# ltc4063-test.net
KiCad netlist of a schematic drawn in EAGLE
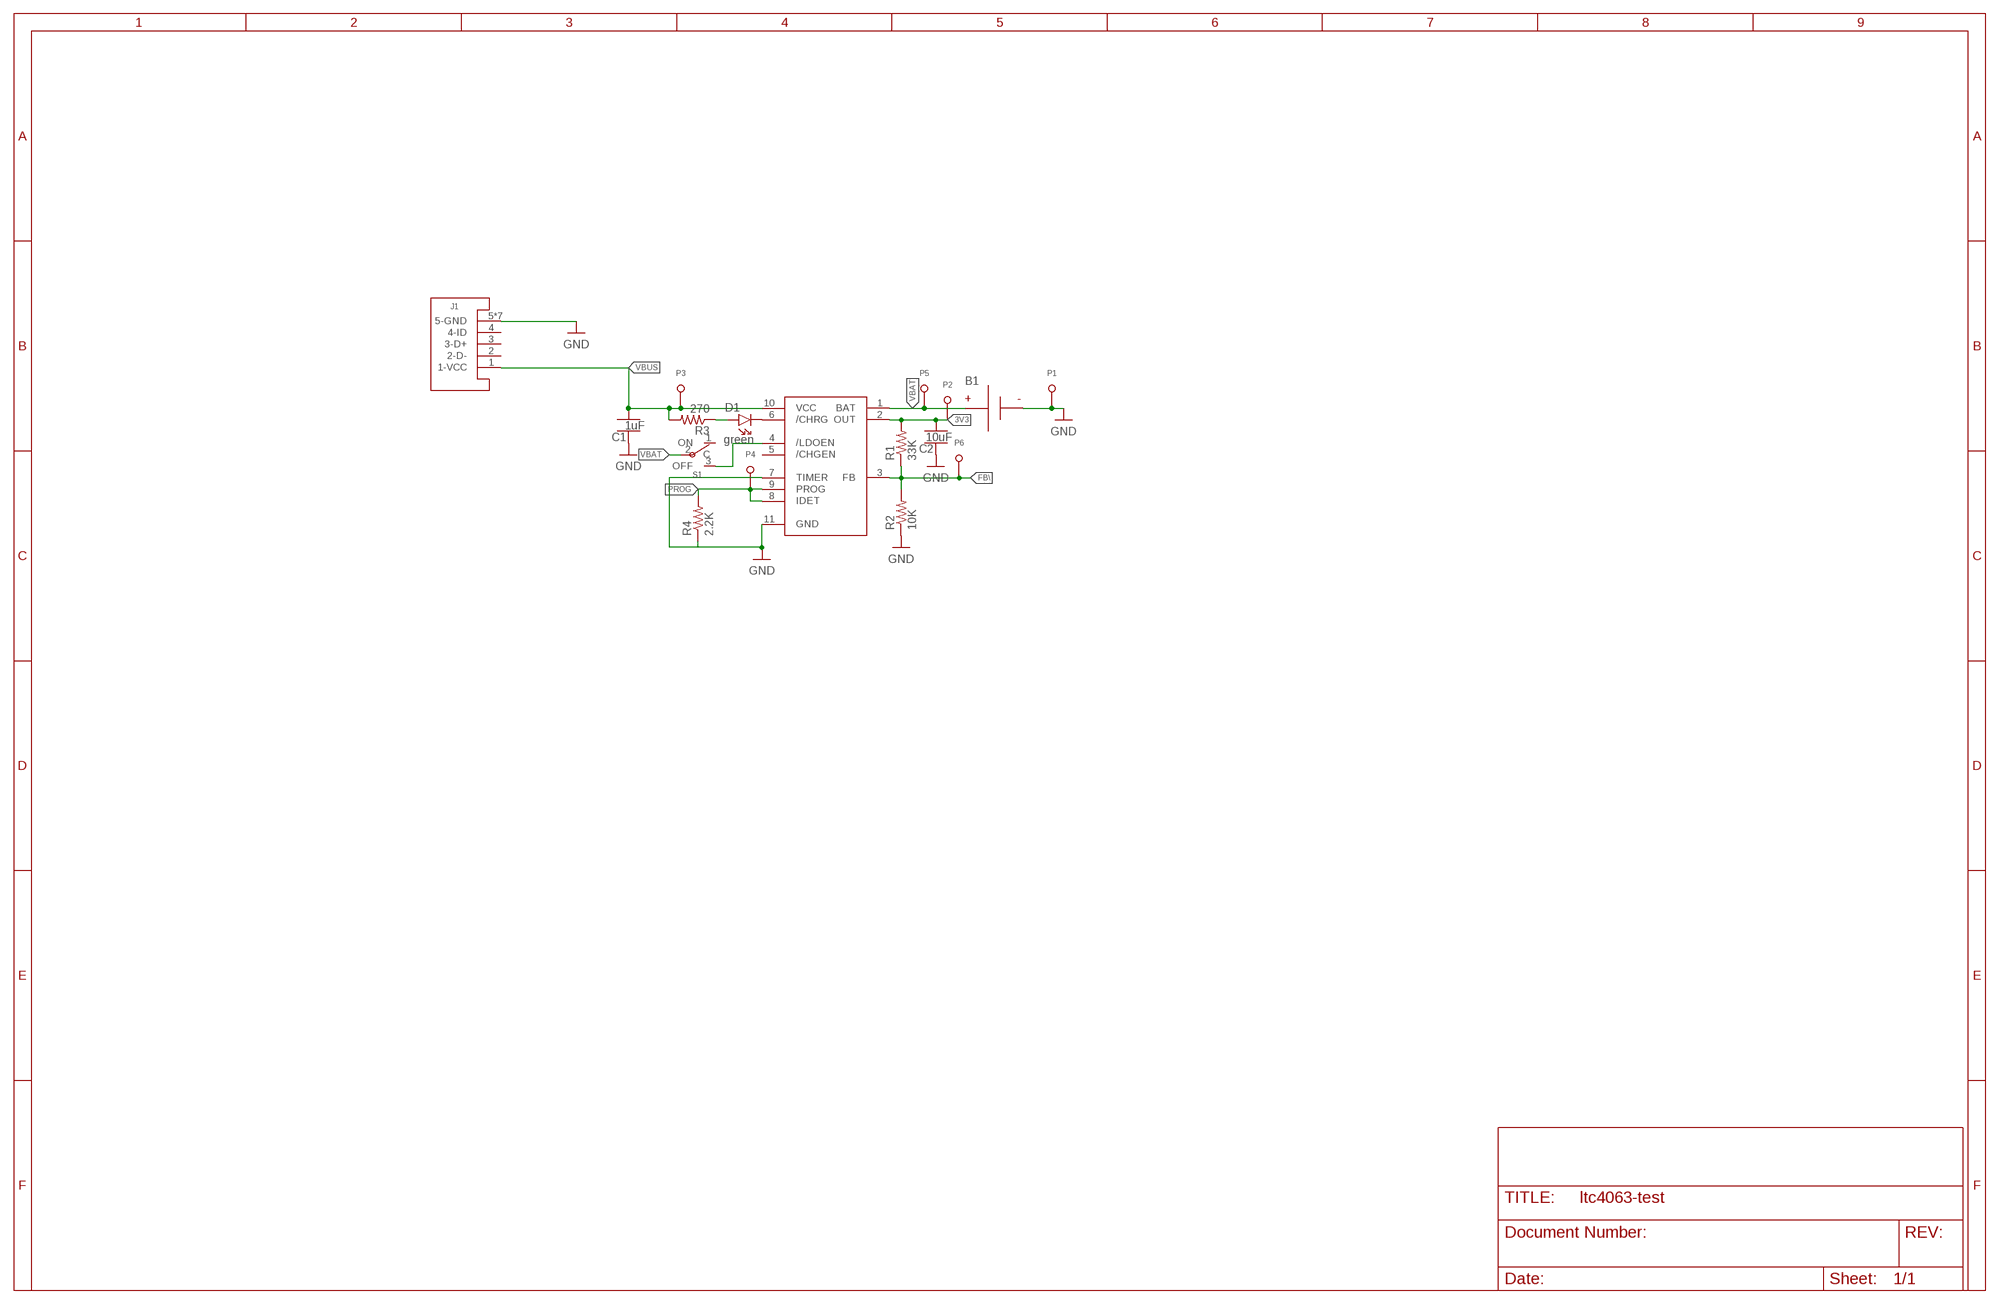
[diagram p0: schematic, sheet 1]

(export (version "E")
  (design (tool "Eeschema 10.0.6"))
  (components
    (comp (ref "B1")
      (value "BATTERY-SPRING-SMD")
      (footprint "eagle-import:WIRE-TERMINAL-1X2-2.5MM-SMD-AVX-009276002021106")
      (libsource (lib "eagle-import") (part "BATTERY-SPRING-SMD"))
    )
    (comp (ref "C1")
      (value "1uF")
      (footprint "eagle-import:CAPC2012X140_HS")
      (fields
        (field (name "MFR") "Taiyo Yuden")
        (field (name "MPN") "TMK212B7105KG-T")
        (field (name "CREATOR") "Swanson")
        (field (name "REVIEWER") "Swanson")
      )
      (libsource (lib "eagle-import") (part "CAPACITOR-NP_SMD-2012-0805_CERAMIC-1UF"))
    )
    (comp (ref "C2")
      (value "10uF")
      (footprint "eagle-import:CAPC2012X140_HS")
      (fields (field (name "CREATOR") "Swanson") (field (name "REVIEWER") "Swanson"))
      (libsource (lib "eagle-import") (part "CAPACITOR-NP_SMD-2012-0805_CERAMIC-10UF"))
    )
    (comp (ref "D1")
      (value "green")
      (footprint "eagle-import:LEDSC125X200X120-2_HS")
      (fields
        (field (name "MFR") "Lite-On Inc")
        (field (name "MPN") "LTST-C170GKT")
        (field (name "CREATOR") "Swanson")
        (field (name "REVIEWER") "Swanson")
      )
      (libsource (lib "eagle-import") (part "DIODE-LED_SMD-2012-0805-GREEN"))
    )
    (comp (ref "J1")
      (value "USB-MICROA-AMPHENOL-10118192-0001LF")
      (footprint "eagle-import:USB-MICROA-10118192-0001LF")
      (fields (field (name "CREATOR") "Swanson"))
      (libsource (lib "eagle-import") (part "USB-MICROA-AMPHENOL-10118192-0001LF"))
    )
    (comp (ref "P1")
      (value "TEST-POINT")
      (footprint "eagle-import:TEST-POINT-KEYSTONE-5000")
      (fields (field (name "CREATOR") "Swanson"))
      (libsource (lib "eagle-import") (part "TEST-POINT"))
    )
    (comp (ref "P2")
      (value "TEST-POINT")
      (footprint "eagle-import:TEST-POINT-KEYSTONE-5000")
      (fields (field (name "CREATOR") "Swanson"))
      (libsource (lib "eagle-import") (part "TEST-POINT"))
    )
    (comp (ref "P3")
      (value "TEST-POINT")
      (footprint "eagle-import:TEST-POINT-KEYSTONE-5000")
      (fields (field (name "CREATOR") "Swanson"))
      (libsource (lib "eagle-import") (part "TEST-POINT"))
    )
    (comp (ref "P4")
      (value "TEST-POINT")
      (footprint "eagle-import:TEST-POINT-KEYSTONE-5000")
      (fields (field (name "CREATOR") "Swanson"))
      (libsource (lib "eagle-import") (part "TEST-POINT"))
    )
    (comp (ref "P5")
      (value "TEST-POINT")
      (footprint "eagle-import:TEST-POINT-KEYSTONE-5000")
      (fields (field (name "CREATOR") "Swanson"))
      (libsource (lib "eagle-import") (part "TEST-POINT"))
    )
    (comp (ref "P6")
      (value "TEST-POINT")
      (footprint "eagle-import:TEST-POINT-KEYSTONE-5000")
      (fields (field (name "CREATOR") "Swanson"))
      (libsource (lib "eagle-import") (part "TEST-POINT"))
    )
    (comp (ref "R1")
      (value "33K")
      (footprint "eagle-import:RESC2012X60_HS")
      (fields (field (name "CREATOR") "SWANSON"))
      (libsource (lib "eagle-import") (part "RESISTOR_SMD-2012-0805-33K"))
    )
    (comp (ref "R2")
      (value "10K")
      (footprint "eagle-import:RESC2012X60_HS")
      (fields
        (field (name "MFR") "Yageo")
        (field (name "MPN") "RC0805JR-0710KL")
        (field (name "CREATOR") "Swanson")
        (field (name "REVIEWER") "Swanson")
      )
      (libsource (lib "eagle-import") (part "RESISTOR_SMD-2012-0805-10K"))
    )
    (comp (ref "R3")
      (value "270")
      (footprint "eagle-import:RESC2012X60_HS")
      (fields (field (name "CREATOR") "SWANSON"))
      (libsource (lib "eagle-import") (part "RESISTOR_SMD-2012-0805-270"))
    )
    (comp (ref "R4")
      (value "2.2K")
      (footprint "eagle-import:RESC2012X60_HS")
      (fields (field (name "CREATOR") "SWANSON"))
      (libsource (lib "eagle-import") (part "RESISTOR_SMD-2012-0805-2.2K"))
    )
    (comp (ref "S1")
      (value "POWER-SWITCH-MFS201N-9-Z-SMD-VERTICAL")
      (footprint "eagle-import:JS102011JCQN")
      (fields (field (name "CREATOR") "Swanson"))
      (libsource (lib "eagle-import") (part "POWER-SWITCH-MFS201N-9-Z-SMD-VERTICAL"))
    )
    (comp (ref "U1")
      (value "LIPO-VREG-LTC4063")
      (footprint "eagle-import:SON50P300X300X80-11T165X238")
      (fields (field (name "CREATOR") "Swanson"))
      (libsource (lib "eagle-import") (part "LIPO-VREG-LTC4063"))
    )
  )
  (nets
    (net (code "1") (name "3V3") (class "Default")
      (node (ref "C2") (pin "2") (pinfunction "2_2") (pintype "passive"))
      (node (ref "P2") (pin "T") (pinfunction "T_T") (pintype "bidirectional"))
      (node (ref "R1") (pin "2") (pinfunction "2_2") (pintype "passive"))
      (node (ref "U1") (pin "2") (pinfunction "OUT_2") (pintype "bidirectional"))
    )
    (net (code "2") (name "FB\\") (class "Default")
      (node (ref "P6") (pin "T") (pinfunction "T_T") (pintype "bidirectional"))
      (node (ref "R1") (pin "1") (pinfunction "1_1") (pintype "passive"))
      (node (ref "R2") (pin "2") (pinfunction "2_2") (pintype "passive"))
      (node (ref "U1") (pin "3") (pinfunction "FB_3") (pintype "bidirectional"))
    )
    (net (code "3") (name "GND") (class "Default")
      (node (ref "B1") (pin "2A") (pinfunction "N_2A") (pintype "bidirectional"))
      (node (ref "B1") (pin "2B") (pinfunction "N_2B") (pintype "bidirectional"))
      (node (ref "C1") (pin "1") (pinfunction "1_1") (pintype "passive"))
      (node (ref "C2") (pin "1") (pinfunction "1_1") (pintype "passive"))
      (node (ref "J1") (pin "10") (pinfunction "5-GND_10") (pintype "bidirectional"))
      (node (ref "J1") (pin "11") (pinfunction "5-GND_11") (pintype "bidirectional"))
      (node (ref "J1") (pin "5") (pinfunction "5-GND_5") (pintype "bidirectional"))
      (node (ref "J1") (pin "6") (pinfunction "5-GND_6") (pintype "bidirectional"))
      (node (ref "J1") (pin "7") (pinfunction "5-GND_7") (pintype "bidirectional"))
      (node (ref "J1") (pin "8") (pinfunction "5-GND_8") (pintype "bidirectional"))
      (node (ref "J1") (pin "9") (pinfunction "5-GND_9") (pintype "bidirectional"))
      (node (ref "P1") (pin "T") (pinfunction "T_T") (pintype "bidirectional"))
      (node (ref "R2") (pin "1") (pinfunction "1_1") (pintype "passive"))
      (node (ref "R4") (pin "1") (pinfunction "1_1") (pintype "passive"))
      (node (ref "U1") (pin "11") (pinfunction "GND_11") (pintype "bidirectional"))
      (node (ref "U1") (pin "7") (pinfunction "TIMER_7") (pintype "bidirectional"))
    )
    (net (code "4") (name "Net-(D1-PadA)") (class "Default")
      (node (ref "D1") (pin "A") (pinfunction "A_A") (pintype "passive"))
      (node (ref "R3") (pin "1") (pinfunction "1_1") (pintype "passive"))
    )
    (net (code "5") (name "Net-(S1-OFF)") (class "Default")
      (node (ref "S1") (pin "3") (pinfunction "OFF_3") (pintype "bidirectional"))
      (node (ref "U1") (pin "4") (pinfunction "/LDOEN_4") (pintype "bidirectional"))
    )
    (net (code "6") (name "Net-(U1-{slash}CHRG)") (class "Default")
      (node (ref "D1") (pin "C") (pinfunction "C_C") (pintype "passive"))
      (node (ref "U1") (pin "6") (pinfunction "/CHRG_6") (pintype "bidirectional"))
    )
    (net (code "7") (name "PROG") (class "Default")
      (node (ref "P4") (pin "T") (pinfunction "T_T") (pintype "bidirectional"))
      (node (ref "R4") (pin "2") (pinfunction "2_2") (pintype "passive"))
      (node (ref "U1") (pin "8") (pinfunction "IDET_8") (pintype "bidirectional"))
      (node (ref "U1") (pin "9") (pinfunction "PROG_9") (pintype "bidirectional"))
    )
    (net (code "8") (name "VBAT") (class "Default")
      (node (ref "B1") (pin "1A") (pinfunction "P_1A") (pintype "bidirectional"))
      (node (ref "B1") (pin "1B") (pinfunction "P_1B") (pintype "bidirectional"))
      (node (ref "P5") (pin "T") (pinfunction "T_T") (pintype "bidirectional"))
      (node (ref "S1") (pin "2") (pinfunction "C_2") (pintype "bidirectional"))
      (node (ref "U1") (pin "1") (pinfunction "BAT_1") (pintype "bidirectional"))
    )
    (net (code "9") (name "VBUS") (class "Default")
      (node (ref "C1") (pin "2") (pinfunction "2_2") (pintype "passive"))
      (node (ref "J1") (pin "1") (pinfunction "1-VCC_1") (pintype "bidirectional"))
      (node (ref "P3") (pin "T") (pinfunction "T_T") (pintype "bidirectional"))
      (node (ref "R3") (pin "2") (pinfunction "2_2") (pintype "passive"))
      (node (ref "U1") (pin "10") (pinfunction "VCC_10") (pintype "bidirectional"))
    )
    (net (code "10") (name "unconnected-(J1-2-D--Pad2)") (class "Default")
      (node (ref "J1") (pin "2") (pinfunction "2-D-_2") (pintype "bidirectional"))
    )
    (net (code "11") (name "unconnected-(J1-3-D+-Pad3)") (class "Default")
      (node (ref "J1") (pin "3") (pinfunction "3-D+_3") (pintype "bidirectional"))
    )
    (net (code "12") (name "unconnected-(J1-4-ID-Pad4)") (class "Default")
      (node (ref "J1") (pin "4") (pinfunction "4-ID_4") (pintype "bidirectional"))
    )
    (net (code "13") (name "unconnected-(S1-ON-Pad1)") (class "Default")
      (node (ref "S1") (pin "1") (pinfunction "ON_1") (pintype "bidirectional"))
    )
    (net (code "14") (name "unconnected-(U1-{slash}CHGEN-Pad5)") (class "Default")
      (node (ref "U1") (pin "5") (pinfunction "/CHGEN_5") (pintype "bidirectional"))
    )
  )
)
